# henryfc_v1_1.net
KiCad netlist of a schematic drawn in EAGLE
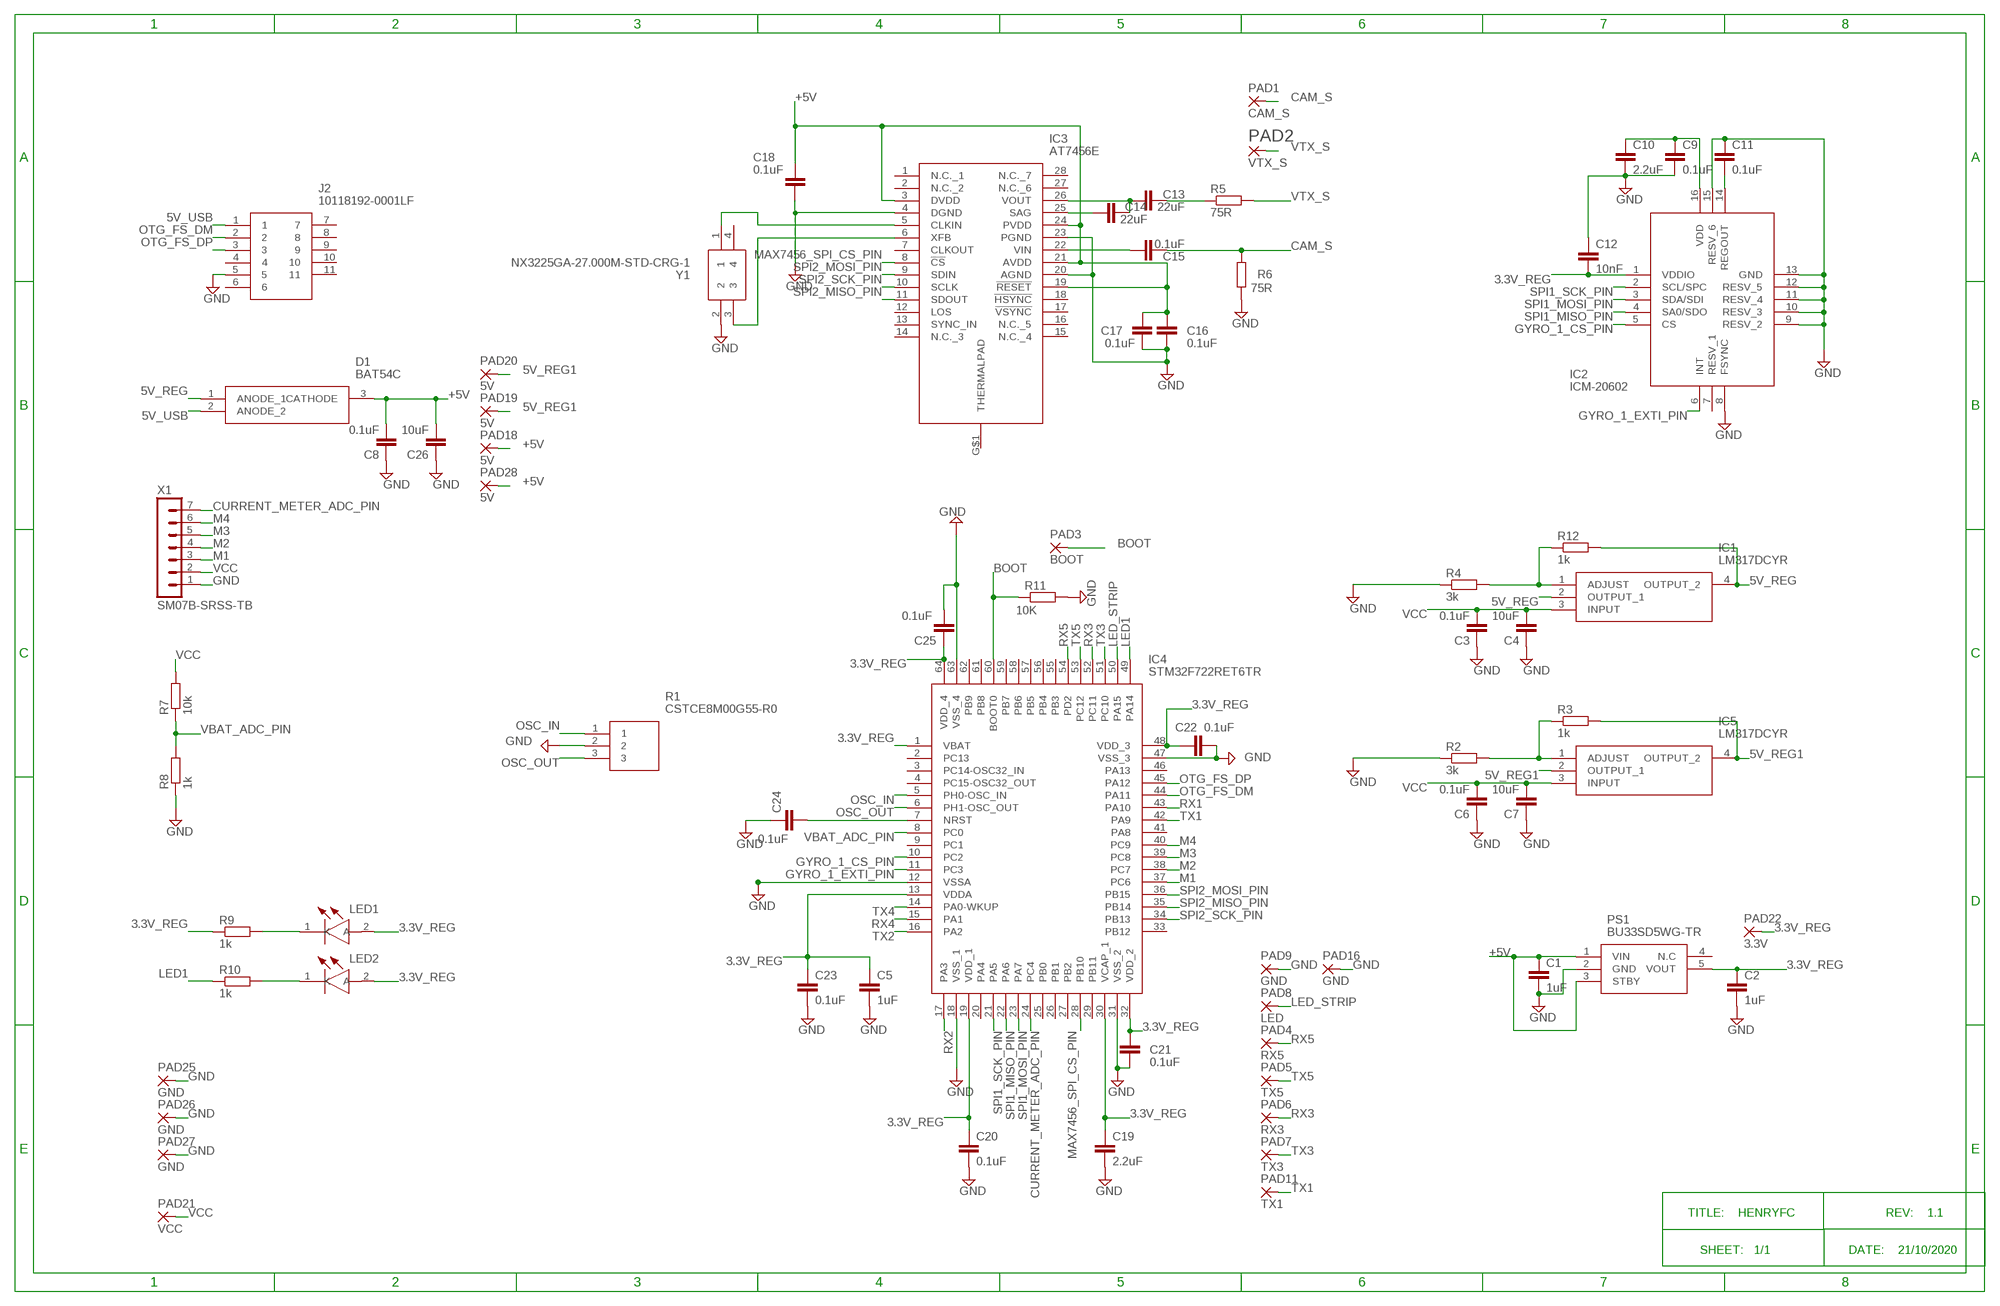
[diagram p0: schematic, sheet 1]

(export (version "E")
  (design (tool "Eeschema 10.0.6"))
  (components
    (comp (ref "C1")
      (value "1uF")
      (footprint "eagle-import:C0603")
      (libsource (lib "eagle-import") (part "C-EUC0603"))
    )
    (comp (ref "C2")
      (value "1uF")
      (footprint "eagle-import:C0603")
      (libsource (lib "eagle-import") (part "C-EUC0603"))
    )
    (comp (ref "C3")
      (value "0.1uF")
      (footprint "eagle-import:C0805")
      (libsource (lib "eagle-import") (part "C-EUC0805"))
    )
    (comp (ref "C4")
      (value "10uF")
      (footprint "eagle-import:C0805")
      (libsource (lib "eagle-import") (part "C-EUC0805"))
    )
    (comp (ref "C5")
      (value "1uF")
      (footprint "eagle-import:C0603")
      (libsource (lib "eagle-import") (part "C-EUC0603"))
    )
    (comp (ref "C6")
      (value "0.1uF")
      (footprint "eagle-import:C0805")
      (libsource (lib "eagle-import") (part "C-EUC0805"))
    )
    (comp (ref "C7")
      (value "10uF")
      (footprint "eagle-import:C0805")
      (libsource (lib "eagle-import") (part "C-EUC0805"))
    )
    (comp (ref "C8")
      (value "0.1uF")
      (footprint "eagle-import:C0805")
      (libsource (lib "eagle-import") (part "C-EUC0805"))
    )
    (comp (ref "C9")
      (value "0.1uF")
      (footprint "eagle-import:C0603")
      (libsource (lib "eagle-import") (part "C-EUC0603"))
    )
    (comp (ref "C10")
      (value "2.2uF")
      (footprint "eagle-import:C0603")
      (libsource (lib "eagle-import") (part "C-EUC0603"))
    )
    (comp (ref "C11")
      (value "0.1uF")
      (footprint "eagle-import:C0603")
      (libsource (lib "eagle-import") (part "C-EUC0603"))
    )
    (comp (ref "C12")
      (value "10nF")
      (footprint "eagle-import:C0603")
      (libsource (lib "eagle-import") (part "C-EUC0603"))
    )
    (comp (ref "C13")
      (value "22uF")
      (footprint "eagle-import:C0603")
      (libsource (lib "eagle-import") (part "C-EUC0603"))
    )
    (comp (ref "C14")
      (value "22uF")
      (footprint "eagle-import:C0603")
      (libsource (lib "eagle-import") (part "C-EUC0603"))
    )
    (comp (ref "C15")
      (value "0.1uF")
      (footprint "eagle-import:C0603")
      (libsource (lib "eagle-import") (part "C-EUC0603"))
    )
    (comp (ref "C16")
      (value "0.1uF")
      (footprint "eagle-import:C0603")
      (libsource (lib "eagle-import") (part "C-EUC0603"))
    )
    (comp (ref "C17")
      (value "0.1uF")
      (footprint "eagle-import:C0603")
      (libsource (lib "eagle-import") (part "C-EUC0603"))
    )
    (comp (ref "C18")
      (value "0.1uF")
      (footprint "eagle-import:C0603")
      (libsource (lib "eagle-import") (part "C-EUC0603"))
    )
    (comp (ref "C19")
      (value "2.2uF")
      (footprint "eagle-import:C0603")
      (libsource (lib "eagle-import") (part "C-EUC0603"))
    )
    (comp (ref "C20")
      (value "0.1uF")
      (footprint "eagle-import:C0603")
      (libsource (lib "eagle-import") (part "C-EUC0603"))
    )
    (comp (ref "C21")
      (value "0.1uF")
      (footprint "eagle-import:C0603")
      (libsource (lib "eagle-import") (part "C-EUC0603"))
    )
    (comp (ref "C22")
      (value "0.1uF")
      (footprint "eagle-import:C0603")
      (libsource (lib "eagle-import") (part "C-EUC0603"))
    )
    (comp (ref "C23")
      (value "0.1uF")
      (footprint "eagle-import:C0603")
      (libsource (lib "eagle-import") (part "C-EUC0603"))
    )
    (comp (ref "C24")
      (value "0.1uF")
      (footprint "eagle-import:C0603")
      (libsource (lib "eagle-import") (part "C-EUC0603"))
    )
    (comp (ref "C25")
      (value "0.1uF")
      (footprint "eagle-import:C0603")
      (libsource (lib "eagle-import") (part "C-EUC0603"))
    )
    (comp (ref "C26")
      (value "10uF")
      (footprint "eagle-import:C0805")
      (libsource (lib "eagle-import") (part "C-EUC0805"))
    )
    (comp (ref "D1")
      (value "BAT54C")
      (footprint "eagle-import:SOT95P240X120-3N")
      (fields (field (name "MOUSER_PART_NUMBER") "512-BAT54C"))
      (libsource (lib "eagle-import") (part "BAT54C"))
    )
    (comp (ref "IC1")
      (value "LM317DCYR")
      (footprint "eagle-import:SOT230P700X180-4N")
      (fields (field (name "MOUSER_PART_NUMBER") "595-LM317DCYR"))
      (libsource (lib "eagle-import") (part "LM317DCYR"))
    )
    (comp (ref "IC2")
      (value "ICM-20602")
      (footprint "eagle-import:PULL-BACK-QFN-16")
      (fields (field (name "MOUSER_PART_NUMBER") "410-ICM-20602"))
      (libsource (lib "eagle-import") (part "ICM-20602"))
    )
    (comp (ref "IC3")
      (value "AT7456E")
      (footprint "eagle-import:SOP65P640X120-29N")
      (libsource (lib "eagle-import") (part "AT7456E"))
    )
    (comp (ref "IC4")
      (value "STM32F722RET6TR")
      (footprint "eagle-import:QFP50P1200X1200X160-64N")
      (fields (field (name "MOUSER_PART_NUMBER") "511-STM32F722RET6TR"))
      (libsource (lib "eagle-import") (part "STM32F722RET6TR"))
    )
    (comp (ref "IC5")
      (value "LM317DCYR")
      (footprint "eagle-import:SOT230P700X180-4N")
      (fields (field (name "MOUSER_PART_NUMBER") "595-LM317DCYR"))
      (libsource (lib "eagle-import") (part "LM317DCYR"))
    )
    (comp (ref "J2")
      (value "10118192-0001LF")
      (footprint "eagle-import:101181920001LF")
      (fields (field (name "MOUSER_PART_NUMBER") "649-10118192-0001LF"))
      (libsource (lib "eagle-import") (part "10118192-0001LF"))
    )
    (comp (ref "LED1")
      (value "KB_DELPS2.12-QHRI-24-Z555-10-S")
      (footprint "eagle-import:KBDELPS212QHRI24Z55510S")
      (fields
        (field (name "ARROW_PART_NUMBER") "KB DELPS2.12-QHRI-24-Z555-10-S")
        (field (name "MOUSER_PART_NUMBER") "720-KBDELPS212A6350")
      )
      (libsource (lib "eagle-import") (part "KB_DELPS2.12-QHRI-24-Z555-10-S"))
    )
    (comp (ref "LED2")
      (value "KR_DELPS1.22-UHVI-26-H3Q4")
      (footprint "eagle-import:KRDELPS122UHVI26H3Q4")
      (fields
        (field (name "ARROW_PART_NUMBER") "KR DELPS1.22-UHVI-26-H3Q4")
        (field (name "MOUSER_PART_NUMBER") "720-KRDELPS122A5163")
      )
      (libsource (lib "eagle-import") (part "KR_DELPS1.22-UHVI-26-H3Q4"))
    )
    (comp (ref "PAD1")
      (value "CAM_S")
      (footprint "eagle-import:SMD1,27-2,54")
      (libsource (lib "eagle-import") (part "SMD2"))
    )
    (comp (ref "PAD2")
      (value "VTX_S")
      (footprint "eagle-import:SMD1,27-2,54")
      (libsource (lib "eagle-import") (part "SMD2"))
    )
    (comp (ref "PAD3")
      (value "BOOT")
      (footprint "eagle-import:SMD1,27-2,54")
      (libsource (lib "eagle-import") (part "SMD2"))
    )
    (comp (ref "PAD4")
      (value "RX5")
      (footprint "eagle-import:SMD1,27-2,54")
      (libsource (lib "eagle-import") (part "SMD2"))
    )
    (comp (ref "PAD5")
      (value "TX5")
      (footprint "eagle-import:SMD1,27-2,54")
      (libsource (lib "eagle-import") (part "SMD2"))
    )
    (comp (ref "PAD6")
      (value "RX3")
      (footprint "eagle-import:SMD1,27-2,54")
      (libsource (lib "eagle-import") (part "SMD2"))
    )
    (comp (ref "PAD7")
      (value "TX3")
      (footprint "eagle-import:SMD1,27-2,54")
      (libsource (lib "eagle-import") (part "SMD2"))
    )
    (comp (ref "PAD8")
      (value "LED")
      (footprint "eagle-import:SMD1,27-2,54")
      (libsource (lib "eagle-import") (part "SMD2"))
    )
    (comp (ref "PAD9")
      (value "GND")
      (footprint "eagle-import:SMD1,27-2,54")
      (libsource (lib "eagle-import") (part "SMD2"))
    )
    (comp (ref "PAD11")
      (value "TX1")
      (footprint "eagle-import:SMD1,27-2,54")
      (libsource (lib "eagle-import") (part "SMD2"))
    )
    (comp (ref "PAD16")
      (value "GND")
      (footprint "eagle-import:SMD1,27-2,54")
      (libsource (lib "eagle-import") (part "SMD2"))
    )
    (comp (ref "PAD18")
      (value "5V")
      (footprint "eagle-import:SMD1,27-2,54")
      (libsource (lib "eagle-import") (part "SMD2"))
    )
    (comp (ref "PAD19")
      (value "5V")
      (footprint "eagle-import:SMD1,27-2,54")
      (libsource (lib "eagle-import") (part "SMD2"))
    )
    (comp (ref "PAD20")
      (value "5V")
      (footprint "eagle-import:SMD1,27-2,54")
      (libsource (lib "eagle-import") (part "SMD2"))
    )
    (comp (ref "PAD21")
      (value "VCC")
      (footprint "eagle-import:SMD1,27-2,54")
      (libsource (lib "eagle-import") (part "SMD2"))
    )
    (comp (ref "PAD22")
      (value "3.3V")
      (footprint "eagle-import:SMD1,27-2,54")
      (libsource (lib "eagle-import") (part "SMD2"))
    )
    (comp (ref "PAD25")
      (value "GND")
      (footprint "eagle-import:SMD1,27-2,54")
      (libsource (lib "eagle-import") (part "SMD2"))
    )
    (comp (ref "PAD26")
      (value "GND")
      (footprint "eagle-import:SMD1,27-2,54")
      (libsource (lib "eagle-import") (part "SMD2"))
    )
    (comp (ref "PAD27")
      (value "GND")
      (footprint "eagle-import:SMD1,27-2,54")
      (libsource (lib "eagle-import") (part "SMD2"))
    )
    (comp (ref "PAD28")
      (value "5V")
      (footprint "eagle-import:SMD1,27-2,54")
      (libsource (lib "eagle-import") (part "SMD2"))
    )
    (comp (ref "PS1")
      (value "BU33SD5WG-TR")
      (footprint "eagle-import:SOT95P280X125-5N")
      (fields (field (name "MOUSER_PART_NUMBER") "755-BU33SD5WG-TR"))
      (libsource (lib "eagle-import") (part "BU33SD5WG-TR"))
    )
    (comp (ref "R1")
      (value "CSTCE8M00G55-R0")
      (footprint "eagle-import:CSTCE12M0G55-R0")
      (fields (field (name "MOUSER_PART_NUMBER") "81-CSTCE8M00G55-R0"))
      (libsource (lib "eagle-import") (part "CSTCE8M00G55-R0"))
    )
    (comp (ref "R2")
      (value "3k")
      (footprint "eagle-import:R0603")
      (libsource (lib "eagle-import") (part "R-EU_R0603"))
    )
    (comp (ref "R3")
      (value "1k")
      (footprint "eagle-import:R0603")
      (libsource (lib "eagle-import") (part "R-EU_R0603"))
    )
    (comp (ref "R4")
      (value "3k")
      (footprint "eagle-import:R0603")
      (libsource (lib "eagle-import") (part "R-EU_R0603"))
    )
    (comp (ref "R5")
      (value "75R")
      (footprint "eagle-import:R0603")
      (libsource (lib "eagle-import") (part "R-EU_R0603"))
    )
    (comp (ref "R6")
      (value "75R")
      (footprint "eagle-import:R0603")
      (libsource (lib "eagle-import") (part "R-EU_R0603"))
    )
    (comp (ref "R7")
      (value "10k")
      (footprint "eagle-import:R0603")
      (libsource (lib "eagle-import") (part "R-EU_R0603"))
    )
    (comp (ref "R8")
      (value "1k")
      (footprint "eagle-import:R0603")
      (libsource (lib "eagle-import") (part "R-EU_R0603"))
    )
    (comp (ref "R9")
      (value "1k")
      (footprint "eagle-import:R0603")
      (libsource (lib "eagle-import") (part "R-EU_R0603"))
    )
    (comp (ref "R10")
      (value "1k")
      (footprint "eagle-import:R0603")
      (libsource (lib "eagle-import") (part "R-EU_R0603"))
    )
    (comp (ref "R11")
      (value "10K")
      (footprint "eagle-import:R0603")
      (libsource (lib "eagle-import") (part "R-EU_R0603"))
    )
    (comp (ref "R12")
      (value "1k")
      (footprint "eagle-import:R0603")
      (libsource (lib "eagle-import") (part "R-EU_R0603"))
    )
    (comp (ref "X1")
      (value "SM07B-SRSS-TB")
      (footprint "eagle-import:SM07B-SRSS-TB")
      (libsource (lib "eagle-import") (part "SM07B-SRSS-TB"))
    )
    (comp (ref "Y1")
      (value "NX3225GA-27.000M-STD-CRG-1")
      (footprint "eagle-import:NX3225GA")
      (fields (field (name "MOUSER_PART_NUMBER") "344-NX3225GA27MSTRG1"))
      (libsource (lib "eagle-import") (part "NX3225GA-27.000M-STD-CRG-1"))
    )
  )
  (nets
    (net (code "1") (name "/+5V") (class "Default")
      (node (ref "C1") (pin "1") (pinfunction "1_1") (pintype "passive"))
      (node (ref "C16") (pin "1") (pinfunction "1_1") (pintype "passive"))
      (node (ref "C17") (pin "1") (pinfunction "1_1") (pintype "passive"))
      (node (ref "C18") (pin "2") (pinfunction "2_2") (pintype "passive"))
      (node (ref "C26") (pin "2") (pinfunction "2_2") (pintype "passive"))
      (node (ref "C8") (pin "2") (pinfunction "2_2") (pintype "passive"))
      (node (ref "D1") (pin "3") (pinfunction "CATHODE_3") (pintype "bidirectional"))
      (node (ref "IC3") (pin "19") (pinfunction "~{RESET}_19") (pintype "bidirectional"))
      (node (ref "IC3") (pin "21") (pinfunction "AVDD_21") (pintype "bidirectional"))
      (node (ref "IC3") (pin "24") (pinfunction "PVDD_24") (pintype "bidirectional"))
      (node (ref "IC3") (pin "3") (pinfunction "DVDD_3") (pintype "bidirectional"))
      (node (ref "PAD18") (pin "1") (pinfunction "P_1") (pintype "passive"))
      (node (ref "PAD28") (pin "1") (pinfunction "P_1") (pintype "passive"))
      (node (ref "PS1") (pin "1") (pinfunction "VIN_1") (pintype "power_in"))
      (node (ref "PS1") (pin "3") (pinfunction "STBY_3") (pintype "input"))
    )
    (net (code "2") (name "/3.3V_REG") (class "Default")
      (node (ref "C12") (pin "2") (pinfunction "2_2") (pintype "passive"))
      (node (ref "C19") (pin "1") (pinfunction "1_1") (pintype "passive"))
      (node (ref "C2") (pin "1") (pinfunction "1_1") (pintype "passive"))
      (node (ref "C20") (pin "1") (pinfunction "1_1") (pintype "passive"))
      (node (ref "C21") (pin "1") (pinfunction "1_1") (pintype "passive"))
      (node (ref "C22") (pin "1") (pinfunction "1_1") (pintype "passive"))
      (node (ref "C23") (pin "1") (pinfunction "1_1") (pintype "passive"))
      (node (ref "C25") (pin "1") (pinfunction "1_1") (pintype "passive"))
      (node (ref "C5") (pin "1") (pinfunction "1_1") (pintype "passive"))
      (node (ref "IC2") (pin "1") (pinfunction "VDDIO_1") (pintype "bidirectional"))
      (node (ref "IC4") (pin "1") (pinfunction "VBAT_1") (pintype "bidirectional"))
      (node (ref "IC4") (pin "13") (pinfunction "VDDA_13") (pintype "bidirectional"))
      (node (ref "IC4") (pin "19") (pinfunction "VDD_1_19") (pintype "bidirectional"))
      (node (ref "IC4") (pin "30") (pinfunction "VCAP_1_30") (pintype "bidirectional"))
      (node (ref "IC4") (pin "32") (pinfunction "VDD_2_32") (pintype "bidirectional"))
      (node (ref "IC4") (pin "48") (pinfunction "VDD_3_48") (pintype "bidirectional"))
      (node (ref "IC4") (pin "64") (pinfunction "VDD_4_64") (pintype "bidirectional"))
      (node (ref "LED1") (pin "2") (pinfunction "A_2") (pintype "bidirectional"))
      (node (ref "LED2") (pin "2") (pinfunction "A_2") (pintype "bidirectional"))
      (node (ref "PAD22") (pin "1") (pinfunction "P_1") (pintype "passive"))
      (node (ref "PS1") (pin "5") (pinfunction "VOUT_5") (pintype "output"))
      (node (ref "R9") (pin "1") (pinfunction "1_1") (pintype "passive"))
    )
    (net (code "3") (name "/5V_REG") (class "Default")
      (node (ref "D1") (pin "1") (pinfunction "ANODE_1_1") (pintype "bidirectional"))
      (node (ref "IC1") (pin "2") (pinfunction "OUTPUT_1_2") (pintype "bidirectional"))
      (node (ref "IC1") (pin "4") (pinfunction "OUTPUT_2_4") (pintype "bidirectional"))
      (node (ref "R12") (pin "2") (pinfunction "2_2") (pintype "passive"))
    )
    (net (code "4") (name "/5V_REG1") (class "Default")
      (node (ref "IC5") (pin "2") (pinfunction "OUTPUT_1_2") (pintype "bidirectional"))
      (node (ref "IC5") (pin "4") (pinfunction "OUTPUT_2_4") (pintype "bidirectional"))
      (node (ref "PAD19") (pin "1") (pinfunction "P_1") (pintype "passive"))
      (node (ref "PAD20") (pin "1") (pinfunction "P_1") (pintype "passive"))
      (node (ref "R3") (pin "2") (pinfunction "2_2") (pintype "passive"))
    )
    (net (code "5") (name "/5V_USB") (class "Default")
      (node (ref "D1") (pin "2") (pinfunction "ANODE_2_2") (pintype "bidirectional"))
      (node (ref "J2") (pin "1") (pinfunction "1_1") (pintype "bidirectional"))
    )
    (net (code "6") (name "/BOOT") (class "Default")
      (node (ref "IC4") (pin "60") (pinfunction "BOOT0_60") (pintype "bidirectional"))
      (node (ref "PAD3") (pin "1") (pinfunction "P_1") (pintype "passive"))
      (node (ref "R11") (pin "1") (pinfunction "1_1") (pintype "passive"))
    )
    (net (code "7") (name "/CAM_S") (class "Default")
      (node (ref "C15") (pin "2") (pinfunction "2_2") (pintype "passive"))
      (node (ref "PAD1") (pin "1") (pinfunction "P_1") (pintype "passive"))
      (node (ref "R6") (pin "2") (pinfunction "2_2") (pintype "passive"))
    )
    (net (code "8") (name "/CURRENT_METER_ADC_PIN") (class "Default")
      (node (ref "IC4") (pin "24") (pinfunction "PC4_24") (pintype "bidirectional"))
      (node (ref "X1") (pin "7") (pinfunction "7_7") (pintype "passive"))
    )
    (net (code "9") (name "/GYRO_1_CS_PIN") (class "Default")
      (node (ref "IC2") (pin "5") (pinfunction "CS_5") (pintype "bidirectional"))
      (node (ref "IC4") (pin "10") (pinfunction "PC2_10") (pintype "bidirectional"))
    )
    (net (code "10") (name "/GYRO_1_EXTI_PIN") (class "Default")
      (node (ref "IC2") (pin "6") (pinfunction "INT_6") (pintype "bidirectional"))
      (node (ref "IC4") (pin "11") (pinfunction "PC3_11") (pintype "bidirectional"))
    )
    (net (code "11") (name "/LED1") (class "Default")
      (node (ref "IC4") (pin "49") (pinfunction "PA14_49") (pintype "bidirectional"))
      (node (ref "R10") (pin "1") (pinfunction "1_1") (pintype "passive"))
    )
    (net (code "12") (name "/LED_STRIP") (class "Default")
      (node (ref "IC4") (pin "50") (pinfunction "PA15_50") (pintype "bidirectional"))
      (node (ref "PAD8") (pin "1") (pinfunction "P_1") (pintype "passive"))
    )
    (net (code "13") (name "/M1") (class "Default")
      (node (ref "IC4") (pin "37") (pinfunction "PC6_37") (pintype "bidirectional"))
      (node (ref "X1") (pin "3") (pinfunction "3_3") (pintype "passive"))
    )
    (net (code "14") (name "/M2") (class "Default")
      (node (ref "IC4") (pin "38") (pinfunction "PC7_38") (pintype "bidirectional"))
      (node (ref "X1") (pin "4") (pinfunction "4_4") (pintype "passive"))
    )
    (net (code "15") (name "/M3") (class "Default")
      (node (ref "IC4") (pin "39") (pinfunction "PC8_39") (pintype "bidirectional"))
      (node (ref "X1") (pin "5") (pinfunction "5_5") (pintype "passive"))
    )
    (net (code "16") (name "/M4") (class "Default")
      (node (ref "IC4") (pin "40") (pinfunction "PC9_40") (pintype "bidirectional"))
      (node (ref "X1") (pin "6") (pinfunction "6_6") (pintype "passive"))
    )
    (net (code "17") (name "/MAX7456_SPI_CS_PIN") (class "Default")
      (node (ref "IC3") (pin "8") (pinfunction "~{CS}_8") (pintype "bidirectional"))
      (node (ref "IC4") (pin "28") (pinfunction "PB10_28") (pintype "bidirectional"))
    )
    (net (code "18") (name "/OSC_IN") (class "Default")
      (node (ref "IC4") (pin "5") (pinfunction "PH0-OSC_IN_5") (pintype "bidirectional"))
      (node (ref "R1") (pin "1") (pinfunction "1_1") (pintype "bidirectional"))
    )
    (net (code "19") (name "/OSC_OUT") (class "Default")
      (node (ref "IC4") (pin "6") (pinfunction "PH1-OSC_OUT_6") (pintype "bidirectional"))
      (node (ref "R1") (pin "3") (pinfunction "3_3") (pintype "bidirectional"))
    )
    (net (code "20") (name "/OTG_FS_DM") (class "Default")
      (node (ref "IC4") (pin "44") (pinfunction "PA11_44") (pintype "bidirectional"))
      (node (ref "J2") (pin "2") (pinfunction "2_2") (pintype "bidirectional"))
    )
    (net (code "21") (name "/OTG_FS_DP") (class "Default")
      (node (ref "IC4") (pin "45") (pinfunction "PA12_45") (pintype "bidirectional"))
      (node (ref "J2") (pin "3") (pinfunction "3_3") (pintype "bidirectional"))
    )
    (net (code "22") (name "/RX1") (class "Default")
      (node (ref "IC4") (pin "43") (pinfunction "PA10_43") (pintype "bidirectional"))
    )
    (net (code "23") (name "/RX2") (class "Default")
      (node (ref "IC4") (pin "17") (pinfunction "PA3_17") (pintype "bidirectional"))
    )
    (net (code "24") (name "/RX3") (class "Default")
      (node (ref "IC4") (pin "52") (pinfunction "PC11_52") (pintype "bidirectional"))
      (node (ref "PAD6") (pin "1") (pinfunction "P_1") (pintype "passive"))
    )
    (net (code "25") (name "/RX4") (class "Default")
      (node (ref "IC4") (pin "15") (pinfunction "PA1_15") (pintype "bidirectional"))
    )
    (net (code "26") (name "/RX5") (class "Default")
      (node (ref "IC4") (pin "54") (pinfunction "PD2_54") (pintype "bidirectional"))
      (node (ref "PAD4") (pin "1") (pinfunction "P_1") (pintype "passive"))
    )
    (net (code "27") (name "/SPI1_MISO_PIN") (class "Default")
      (node (ref "IC2") (pin "4") (pinfunction "SA0/SDO_4") (pintype "bidirectional"))
      (node (ref "IC4") (pin "22") (pinfunction "PA6_22") (pintype "bidirectional"))
    )
    (net (code "28") (name "/SPI1_MOSI_PIN") (class "Default")
      (node (ref "IC2") (pin "3") (pinfunction "SDA/SDI_3") (pintype "bidirectional"))
      (node (ref "IC4") (pin "23") (pinfunction "PA7_23") (pintype "bidirectional"))
    )
    (net (code "29") (name "/SPI1_SCK_PIN") (class "Default")
      (node (ref "IC2") (pin "2") (pinfunction "SCL/SPC_2") (pintype "bidirectional"))
      (node (ref "IC4") (pin "21") (pinfunction "PA5_21") (pintype "bidirectional"))
    )
    (net (code "30") (name "/SPI2_MISO_PIN") (class "Default")
      (node (ref "IC3") (pin "11") (pinfunction "SDOUT_11") (pintype "bidirectional"))
      (node (ref "IC4") (pin "35") (pinfunction "PB14_35") (pintype "bidirectional"))
    )
    (net (code "31") (name "/SPI2_MOSI_PIN") (class "Default")
      (node (ref "IC3") (pin "9") (pinfunction "SDIN_9") (pintype "bidirectional"))
      (node (ref "IC4") (pin "36") (pinfunction "PB15_36") (pintype "bidirectional"))
    )
    (net (code "32") (name "/SPI2_SCK_PIN") (class "Default")
      (node (ref "IC3") (pin "10") (pinfunction "SCLK_10") (pintype "bidirectional"))
      (node (ref "IC4") (pin "34") (pinfunction "PB13_34") (pintype "bidirectional"))
    )
    (net (code "33") (name "/TX1") (class "Default")
      (node (ref "IC4") (pin "42") (pinfunction "PA9_42") (pintype "bidirectional"))
      (node (ref "PAD11") (pin "1") (pinfunction "P_1") (pintype "passive"))
    )
    (net (code "34") (name "/TX2") (class "Default")
      (node (ref "IC4") (pin "16") (pinfunction "PA2_16") (pintype "bidirectional"))
    )
    (net (code "35") (name "/TX3") (class "Default")
      (node (ref "IC4") (pin "51") (pinfunction "PC10_51") (pintype "bidirectional"))
      (node (ref "PAD7") (pin "1") (pinfunction "P_1") (pintype "passive"))
    )
    (net (code "36") (name "/TX4") (class "Default")
      (node (ref "IC4") (pin "14") (pinfunction "PA0-WKUP_14") (pintype "bidirectional"))
    )
    (net (code "37") (name "/TX5") (class "Default")
      (node (ref "IC4") (pin "53") (pinfunction "PC12_53") (pintype "bidirectional"))
      (node (ref "PAD5") (pin "1") (pinfunction "P_1") (pintype "passive"))
    )
    (net (code "38") (name "/VBAT_ADC_PIN") (class "Default")
      (node (ref "IC4") (pin "8") (pinfunction "PC0_8") (pintype "bidirectional"))
      (node (ref "R7") (pin "1") (pinfunction "1_1") (pintype "passive"))
      (node (ref "R8") (pin "2") (pinfunction "2_2") (pintype "passive"))
    )
    (net (code "39") (name "/VCC") (class "Default")
      (node (ref "C3") (pin "2") (pinfunction "2_2") (pintype "passive"))
      (node (ref "C4") (pin "2") (pinfunction "2_2") (pintype "passive"))
      (node (ref "C6") (pin "2") (pinfunction "2_2") (pintype "passive"))
      (node (ref "C7") (pin "2") (pinfunction "2_2") (pintype "passive"))
      (node (ref "IC1") (pin "3") (pinfunction "INPUT_3") (pintype "bidirectional"))
      (node (ref "IC5") (pin "3") (pinfunction "INPUT_3") (pintype "bidirectional"))
      (node (ref "PAD21") (pin "1") (pinfunction "P_1") (pintype "passive"))
      (node (ref "R7") (pin "2") (pinfunction "2_2") (pintype "passive"))
      (node (ref "X1") (pin "2") (pinfunction "2_2") (pintype "passive"))
    )
    (net (code "40") (name "/VTX_S") (class "Default")
      (node (ref "PAD2") (pin "1") (pinfunction "P_1") (pintype "passive"))
      (node (ref "R5") (pin "2") (pinfunction "2_2") (pintype "passive"))
    )
    (net (code "41") (name "GND") (class "Default")
      (node (ref "C1") (pin "2") (pinfunction "2_2") (pintype "passive"))
      (node (ref "C10") (pin "2") (pinfunction "2_2") (pintype "passive"))
      (node (ref "C11") (pin "1") (pinfunction "1_1") (pintype "passive"))
      (node (ref "C12") (pin "1") (pinfunction "1_1") (pintype "passive"))
      (node (ref "C16") (pin "2") (pinfunction "2_2") (pintype "passive"))
      (node (ref "C17") (pin "2") (pinfunction "2_2") (pintype "passive"))
      (node (ref "C18") (pin "1") (pinfunction "1_1") (pintype "passive"))
      (node (ref "C19") (pin "2") (pinfunction "2_2") (pintype "passive"))
      (node (ref "C2") (pin "2") (pinfunction "2_2") (pintype "passive"))
      (node (ref "C20") (pin "2") (pinfunction "2_2") (pintype "passive"))
      (node (ref "C21") (pin "2") (pinfunction "2_2") (pintype "passive"))
      (node (ref "C22") (pin "2") (pinfunction "2_2") (pintype "passive"))
      (node (ref "C23") (pin "2") (pinfunction "2_2") (pintype "passive"))
      (node (ref "C24") (pin "1") (pinfunction "1_1") (pintype "passive"))
      (node (ref "C25") (pin "2") (pinfunction "2_2") (pintype "passive"))
      (node (ref "C26") (pin "1") (pinfunction "1_1") (pintype "passive"))
      (node (ref "C3") (pin "1") (pinfunction "1_1") (pintype "passive"))
      (node (ref "C4") (pin "1") (pinfunction "1_1") (pintype "passive"))
      (node (ref "C5") (pin "2") (pinfunction "2_2") (pintype "passive"))
      (node (ref "C6") (pin "1") (pinfunction "1_1") (pintype "passive"))
      (node (ref "C7") (pin "1") (pinfunction "1_1") (pintype "passive"))
      (node (ref "C8") (pin "1") (pinfunction "1_1") (pintype "passive"))
      (node (ref "C9") (pin "2") (pinfunction "2_2") (pintype "passive"))
      (node (ref "IC2") (pin "10") (pinfunction "RESV_3_10") (pintype "bidirectional"))
      (node (ref "IC2") (pin "11") (pinfunction "RESV_4_11") (pintype "bidirectional"))
      (node (ref "IC2") (pin "12") (pinfunction "RESV_5_12") (pintype "bidirectional"))
      (node (ref "IC2") (pin "13") (pinfunction "GND_13") (pintype "bidirectional"))
      (node (ref "IC2") (pin "15") (pinfunction "RESV_6_15") (pintype "bidirectional"))
      (node (ref "IC2") (pin "8") (pinfunction "FSYNC_8") (pintype "bidirectional"))
      (node (ref "IC2") (pin "9") (pinfunction "RESV_2_9") (pintype "bidirectional"))
      (node (ref "IC3") (pin "20") (pinfunction "AGND_20") (pintype "bidirectional"))
      (node (ref "IC3") (pin "23") (pinfunction "PGND_23") (pintype "bidirectional"))
      (node (ref "IC3") (pin "4") (pinfunction "DGND_4") (pintype "bidirectional"))
      (node (ref "IC4") (pin "12") (pinfunction "VSSA_12") (pintype "bidirectional"))
      (node (ref "IC4") (pin "18") (pinfunction "VSS_1_18") (pintype "bidirectional"))
      (node (ref "IC4") (pin "31") (pinfunction "VSS_2_31") (pintype "bidirectional"))
      (node (ref "IC4") (pin "47") (pinfunction "VSS_3_47") (pintype "bidirectional"))
      (node (ref "IC4") (pin "63") (pinfunction "VSS_4_63") (pintype "bidirectional"))
      (node (ref "J2") (pin "5") (pinfunction "5_5") (pintype "bidirectional"))
      (node (ref "PAD16") (pin "1") (pinfunction "P_1") (pintype "passive"))
      (node (ref "PAD25") (pin "1") (pinfunction "P_1") (pintype "passive"))
      (node (ref "PAD26") (pin "1") (pinfunction "P_1") (pintype "passive"))
      (node (ref "PAD27") (pin "1") (pinfunction "P_1") (pintype "passive"))
      (node (ref "PAD9") (pin "1") (pinfunction "P_1") (pintype "passive"))
      (node (ref "PS1") (pin "2") (pinfunction "GND_2") (pintype "power_in"))
      (node (ref "R1") (pin "2") (pinfunction "2_2") (pintype "bidirectional"))
      (node (ref "R11") (pin "2") (pinfunction "2_2") (pintype "passive"))
      (node (ref "R2") (pin "1") (pinfunction "1_1") (pintype "passive"))
      (node (ref "R4") (pin "1") (pinfunction "1_1") (pintype "passive"))
      (node (ref "R6") (pin "1") (pinfunction "1_1") (pintype "passive"))
      (node (ref "R8") (pin "1") (pinfunction "1_1") (pintype "passive"))
      (node (ref "X1") (pin "1") (pinfunction "1_1") (pintype "passive"))
      (node (ref "Y1") (pin "2") (pinfunction "2_2") (pintype "bidirectional"))
    )
    (net (code "42") (name "Net-(C13-Pad2)") (class "Default")
      (node (ref "C13") (pin "2") (pinfunction "2_2") (pintype "passive"))
      (node (ref "R5") (pin "1") (pinfunction "1_1") (pintype "passive"))
    )
    (net (code "43") (name "Net-(IC1-ADJUST)") (class "Default")
      (node (ref "IC1") (pin "1") (pinfunction "ADJUST_1") (pintype "bidirectional"))
      (node (ref "R12") (pin "1") (pinfunction "1_1") (pintype "passive"))
      (node (ref "R4") (pin "2") (pinfunction "2_2") (pintype "passive"))
    )
    (net (code "44") (name "Net-(IC2-REGOUT)") (class "Default")
      (node (ref "C11") (pin "2") (pinfunction "2_2") (pintype "passive"))
      (node (ref "IC2") (pin "14") (pinfunction "REGOUT_14") (pintype "bidirectional"))
    )
    (net (code "45") (name "Net-(IC2-VDD)") (class "Default")
      (node (ref "C10") (pin "1") (pinfunction "1_1") (pintype "passive"))
      (node (ref "C9") (pin "1") (pinfunction "1_1") (pintype "passive"))
      (node (ref "IC2") (pin "16") (pinfunction "VDD_16") (pintype "bidirectional"))
    )
    (net (code "46") (name "Net-(IC3-CLKIN)") (class "Default")
      (node (ref "IC3") (pin "5") (pinfunction "CLKIN_5") (pintype "bidirectional"))
      (node (ref "Y1") (pin "1") (pinfunction "1_1") (pintype "bidirectional"))
    )
    (net (code "47") (name "Net-(IC3-SAG)") (class "Default")
      (node (ref "C14") (pin "1") (pinfunction "1_1") (pintype "passive"))
      (node (ref "IC3") (pin "25") (pinfunction "SAG_25") (pintype "bidirectional"))
    )
    (net (code "48") (name "Net-(IC3-VIN)") (class "Default")
      (node (ref "C15") (pin "1") (pinfunction "1_1") (pintype "passive"))
      (node (ref "IC3") (pin "22") (pinfunction "VIN_22") (pintype "bidirectional"))
    )
    (net (code "49") (name "Net-(IC3-VOUT)") (class "Default")
      (node (ref "C13") (pin "1") (pinfunction "1_1") (pintype "passive"))
      (node (ref "C14") (pin "2") (pinfunction "2_2") (pintype "passive"))
      (node (ref "IC3") (pin "26") (pinfunction "VOUT_26") (pintype "bidirectional"))
    )
    (net (code "50") (name "Net-(IC3-XFB)") (class "Default")
      (node (ref "IC3") (pin "6") (pinfunction "XFB_6") (pintype "bidirectional"))
      (node (ref "Y1") (pin "3") (pinfunction "3_3") (pintype "bidirectional"))
    )
    (net (code "51") (name "Net-(IC4-NRST)") (class "Default")
      (node (ref "C24") (pin "2") (pinfunction "2_2") (pintype "passive"))
      (node (ref "IC4") (pin "7") (pinfunction "NRST_7") (pintype "bidirectional"))
    )
    (net (code "52") (name "Net-(IC5-ADJUST)") (class "Default")
      (node (ref "IC5") (pin "1") (pinfunction "ADJUST_1") (pintype "bidirectional"))
      (node (ref "R2") (pin "2") (pinfunction "2_2") (pintype "passive"))
      (node (ref "R3") (pin "1") (pinfunction "1_1") (pintype "passive"))
    )
    (net (code "53") (name "Net-(LED1-K)") (class "Default")
      (node (ref "LED1") (pin "1") (pinfunction "K_1") (pintype "bidirectional"))
      (node (ref "R9") (pin "2") (pinfunction "2_2") (pintype "passive"))
    )
    (net (code "54") (name "Net-(LED2-K)") (class "Default")
      (node (ref "LED2") (pin "1") (pinfunction "K_1") (pintype "bidirectional"))
      (node (ref "R10") (pin "2") (pinfunction "2_2") (pintype "passive"))
    )
    (net (code "55") (name "unconnected-(IC2-RESV_1-Pad7)") (class "Default")
      (node (ref "IC2") (pin "7") (pinfunction "RESV_1_7") (pintype "bidirectional"))
    )
    (net (code "56") (name "unconnected-(IC3-CLKOUT-Pad7)") (class "Default")
      (node (ref "IC3") (pin "7") (pinfunction "CLKOUT_7") (pintype "bidirectional"))
    )
    (net (code "57") (name "unconnected-(IC3-LOS-Pad12)") (class "Default")
      (node (ref "IC3") (pin "12") (pinfunction "LOS_12") (pintype "bidirectional"))
    )
    (net (code "58") (name "unconnected-(IC3-N.C._1-Pad1)") (class "Default")
      (node (ref "IC3") (pin "1") (pinfunction "N.C._1_1") (pintype "bidirectional"))
    )
    (net (code "59") (name "unconnected-(IC3-N.C._2-Pad2)") (class "Default")
      (node (ref "IC3") (pin "2") (pinfunction "N.C._2_2") (pintype "bidirectional"))
    )
    (net (code "60") (name "unconnected-(IC3-N.C._3-Pad14)") (class "Default")
      (node (ref "IC3") (pin "14") (pinfunction "N.C._3_14") (pintype "bidirectional"))
    )
    (net (code "61") (name "unconnected-(IC3-N.C._4-Pad15)") (class "Default")
      (node (ref "IC3") (pin "15") (pinfunction "N.C._4_15") (pintype "bidirectional"))
    )
    (net (code "62") (name "unconnected-(IC3-N.C._5-Pad16)") (class "Default")
      (node (ref "IC3") (pin "16") (pinfunction "N.C._5_16") (pintype "bidirectional"))
    )
    (net (code "63") (name "unconnected-(IC3-N.C._6-Pad27)") (class "Default")
      (node (ref "IC3") (pin "27") (pinfunction "N.C._6_27") (pintype "bidirectional"))
    )
    (net (code "64") (name "unconnected-(IC3-N.C._7-Pad28)") (class "Default")
      (node (ref "IC3") (pin "28") (pinfunction "N.C._7_28") (pintype "bidirectional"))
    )
    (net (code "65") (name "unconnected-(IC3-SYNC_IN-Pad13)") (class "Default")
      (node (ref "IC3") (pin "13") (pinfunction "SYNC_IN_13") (pintype "bidirectional"))
    )
    (net (code "66") (name "unconnected-(IC3-THERMALPAD-PadG$1)") (class "Default")
      (node (ref "IC3") (pin "G$1") (pinfunction "THERMALPAD_G$1") (pintype "bidirectional"))
    )
    (net (code "67") (name "unconnected-(IC3-~{HSYNC}-Pad18)") (class "Default")
      (node (ref "IC3") (pin "18") (pinfunction "~{HSYNC}_18") (pintype "bidirectional"))
    )
    (net (code "68") (name "unconnected-(IC3-~{VSYNC}-Pad17)") (class "Default")
      (node (ref "IC3") (pin "17") (pinfunction "~{VSYNC}_17") (pintype "bidirectional"))
    )
    (net (code "69") (name "unconnected-(IC4-PA4-Pad20)") (class "Default")
      (node (ref "IC4") (pin "20") (pinfunction "PA4_20") (pintype "bidirectional"))
    )
    (net (code "70") (name "unconnected-(IC4-PA8-Pad41)") (class "Default")
      (node (ref "IC4") (pin "41") (pinfunction "PA8_41") (pintype "bidirectional"))
    )
    (net (code "71") (name "unconnected-(IC4-PA13-Pad46)") (class "Default")
      (node (ref "IC4") (pin "46") (pinfunction "PA13_46") (pintype "bidirectional"))
    )
    (net (code "72") (name "unconnected-(IC4-PB0-Pad25)") (class "Default")
      (node (ref "IC4") (pin "25") (pinfunction "PB0_25") (pintype "bidirectional"))
    )
    (net (code "73") (name "unconnected-(IC4-PB1-Pad26)") (class "Default")
      (node (ref "IC4") (pin "26") (pinfunction "PB1_26") (pintype "bidirectional"))
    )
    (net (code "74") (name "unconnected-(IC4-PB2-Pad27)") (class "Default")
      (node (ref "IC4") (pin "27") (pinfunction "PB2_27") (pintype "bidirectional"))
    )
    (net (code "75") (name "unconnected-(IC4-PB3-Pad55)") (class "Default")
      (node (ref "IC4") (pin "55") (pinfunction "PB3_55") (pintype "bidirectional"))
    )
    (net (code "76") (name "unconnected-(IC4-PB4-Pad56)") (class "Default")
      (node (ref "IC4") (pin "56") (pinfunction "PB4_56") (pintype "bidirectional"))
    )
    (net (code "77") (name "unconnected-(IC4-PB5-Pad57)") (class "Default")
      (node (ref "IC4") (pin "57") (pinfunction "PB5_57") (pintype "bidirectional"))
    )
    (net (code "78") (name "unconnected-(IC4-PB6-Pad58)") (class "Default")
      (node (ref "IC4") (pin "58") (pinfunction "PB6_58") (pintype "bidirectional"))
    )
    (net (code "79") (name "unconnected-(IC4-PB7-Pad59)") (class "Default")
      (node (ref "IC4") (pin "59") (pinfunction "PB7_59") (pintype "bidirectional"))
    )
    (net (code "80") (name "unconnected-(IC4-PB8-Pad61)") (class "Default")
      (node (ref "IC4") (pin "61") (pinfunction "PB8_61") (pintype "bidirectional"))
    )
    (net (code "81") (name "unconnected-(IC4-PB9-Pad62)") (class "Default")
      (node (ref "IC4") (pin "62") (pinfunction "PB9_62") (pintype "bidirectional"))
    )
    (net (code "82") (name "unconnected-(IC4-PB11-Pad29)") (class "Default")
      (node (ref "IC4") (pin "29") (pinfunction "PB11_29") (pintype "bidirectional"))
    )
    (net (code "83") (name "unconnected-(IC4-PB12-Pad33)") (class "Default")
      (node (ref "IC4") (pin "33") (pinfunction "PB12_33") (pintype "bidirectional"))
    )
    (net (code "84") (name "unconnected-(IC4-PC1-Pad9)") (class "Default")
      (node (ref "IC4") (pin "9") (pinfunction "PC1_9") (pintype "bidirectional"))
    )
    (net (code "85") (name "unconnected-(IC4-PC13-Pad2)") (class "Default")
      (node (ref "IC4") (pin "2") (pinfunction "PC13_2") (pintype "bidirectional"))
    )
    (net (code "86") (name "unconnected-(IC4-PC14-OSC32_IN-Pad3)") (class "Default")
      (node (ref "IC4") (pin "3") (pinfunction "PC14-OSC32_IN_3") (pintype "bidirectional"))
    )
    (net (code "87") (name "unconnected-(IC4-PC15-OSC32_OUT-Pad4)") (class "Default")
      (node (ref "IC4") (pin "4") (pinfunction "PC15-OSC32_OUT_4") (pintype "bidirectional"))
    )
    (net (code "88") (name "unconnected-(J2-Pad4)") (class "Default")
      (node (ref "J2") (pin "4") (pinfunction "4_4") (pintype "bidirectional"))
    )
    (net (code "89") (name "unconnected-(J2-Pad6)") (class "Default")
      (node (ref "J2") (pin "6") (pinfunction "6_6") (pintype "bidirectional"))
    )
    (net (code "90") (name "unconnected-(J2-Pad7)") (class "Default")
      (node (ref "J2") (pin "7") (pinfunction "7_7") (pintype "bidirectional"))
    )
    (net (code "91") (name "unconnected-(J2-Pad8)") (class "Default")
      (node (ref "J2") (pin "8") (pinfunction "8_8") (pintype "bidirectional"))
    )
    (net (code "92") (name "unconnected-(J2-Pad9)") (class "Default")
      (node (ref "J2") (pin "9") (pinfunction "9_9") (pintype "bidirectional"))
    )
    (net (code "93") (name "unconnected-(J2-Pad10)") (class "Default")
      (node (ref "J2") (pin "10") (pinfunction "10_10") (pintype "bidirectional"))
    )
    (net (code "94") (name "unconnected-(J2-Pad11)") (class "Default")
      (node (ref "J2") (pin "11") (pinfunction "11_11") (pintype "bidirectional"))
    )
    (net (code "95") (name "unconnected-(PS1-N.C-Pad4)") (class "Default")
      (node (ref "PS1") (pin "4") (pinfunction "N.C_4") (pintype "no_connect"))
    )
    (net (code "96") (name "unconnected-(Y1-Pad4)") (class "Default")
      (node (ref "Y1") (pin "4") (pinfunction "4_4") (pintype "bidirectional"))
    )
  )
)
